# breakout_v3.net
KiCad netlist of a schematic drawn in EAGLE
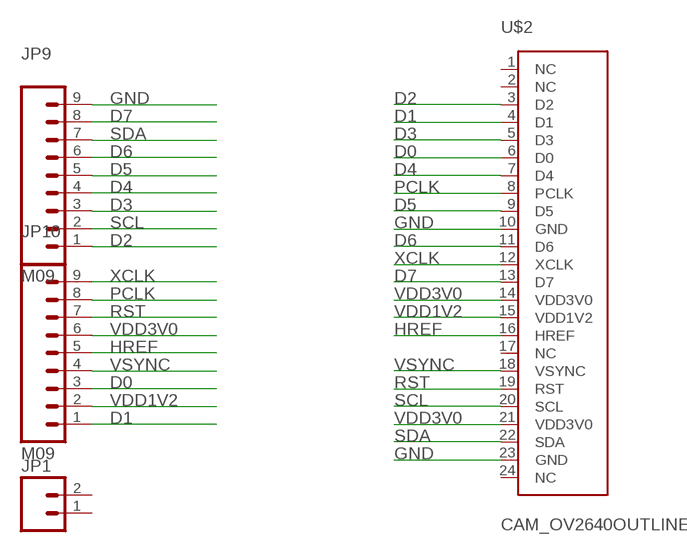
[diagram p0: schematic, sheet 1]

(export (version "E")
  (design (tool "Eeschema 10.0.6"))
  (components
    (comp (ref "JP1")
      (value "M02PTH")
      (footprint "eagle-import:1X02")
      (libsource (lib "eagle-import") (part "M02PTH"))
    )
    (comp (ref "JP9")
      (value "M09")
      (footprint "eagle-import:1X09")
      (libsource (lib "eagle-import") (part "M09"))
    )
    (comp (ref "JP10")
      (value "M09")
      (footprint "eagle-import:1X09")
      (libsource (lib "eagle-import") (part "M09"))
    )
    (comp (ref "U$2")
      (value "CAM_OV2640OUTLINE")
      (footprint "eagle-import:CAM_CONN")
      (libsource (lib "eagle-import") (part "CAM_OV2640OUTLINE"))
    )
  )
  (nets
    (net (code "1") (name "/D0") (class "Default")
      (node (ref "JP10") (pin "3") (pinfunction "3_3") (pintype "passive"))
      (node (ref "U$2") (pin "6") (pinfunction "D0_6") (pintype "bidirectional"))
    )
    (net (code "2") (name "/D1") (class "Default")
      (node (ref "JP10") (pin "1") (pinfunction "1_1") (pintype "passive"))
      (node (ref "U$2") (pin "4") (pinfunction "D1_4") (pintype "bidirectional"))
    )
    (net (code "3") (name "/D2") (class "Default")
      (node (ref "JP9") (pin "1") (pinfunction "1_1") (pintype "passive"))
      (node (ref "U$2") (pin "3") (pinfunction "D2_3") (pintype "bidirectional"))
    )
    (net (code "4") (name "/D3") (class "Default")
      (node (ref "JP9") (pin "3") (pinfunction "3_3") (pintype "passive"))
      (node (ref "U$2") (pin "5") (pinfunction "D3_5") (pintype "bidirectional"))
    )
    (net (code "5") (name "/D4") (class "Default")
      (node (ref "JP9") (pin "4") (pinfunction "4_4") (pintype "passive"))
      (node (ref "U$2") (pin "7") (pinfunction "D4_7") (pintype "bidirectional"))
    )
    (net (code "6") (name "/D5") (class "Default")
      (node (ref "JP9") (pin "5") (pinfunction "5_5") (pintype "passive"))
      (node (ref "U$2") (pin "9") (pinfunction "D5_9") (pintype "bidirectional"))
    )
    (net (code "7") (name "/D6") (class "Default")
      (node (ref "JP9") (pin "6") (pinfunction "6_6") (pintype "passive"))
      (node (ref "U$2") (pin "11") (pinfunction "D6_11") (pintype "bidirectional"))
    )
    (net (code "8") (name "/D7") (class "Default")
      (node (ref "JP9") (pin "8") (pinfunction "8_8") (pintype "passive"))
      (node (ref "U$2") (pin "13") (pinfunction "D7_13") (pintype "bidirectional"))
    )
    (net (code "9") (name "/GND") (class "Default")
      (node (ref "JP9") (pin "9") (pinfunction "9_9") (pintype "passive"))
      (node (ref "U$2") (pin "10") (pinfunction "GND_10") (pintype "bidirectional"))
      (node (ref "U$2") (pin "23") (pinfunction "GND_23") (pintype "bidirectional"))
    )
    (net (code "10") (name "/HREF") (class "Default")
      (node (ref "JP10") (pin "5") (pinfunction "5_5") (pintype "passive"))
      (node (ref "U$2") (pin "16") (pinfunction "HREF_16") (pintype "bidirectional"))
    )
    (net (code "11") (name "/PCLK") (class "Default")
      (node (ref "JP10") (pin "8") (pinfunction "8_8") (pintype "passive"))
      (node (ref "U$2") (pin "8") (pinfunction "PCLK_8") (pintype "bidirectional"))
    )
    (net (code "12") (name "/RST") (class "Default")
      (node (ref "JP10") (pin "7") (pinfunction "7_7") (pintype "passive"))
      (node (ref "U$2") (pin "19") (pinfunction "RST_19") (pintype "bidirectional"))
    )
    (net (code "13") (name "/SCL") (class "Default")
      (node (ref "JP9") (pin "2") (pinfunction "2_2") (pintype "passive"))
      (node (ref "U$2") (pin "20") (pinfunction "SCL_20") (pintype "bidirectional"))
    )
    (net (code "14") (name "/SDA") (class "Default")
      (node (ref "JP9") (pin "7") (pinfunction "7_7") (pintype "passive"))
      (node (ref "U$2") (pin "22") (pinfunction "SDA_22") (pintype "bidirectional"))
    )
    (net (code "15") (name "/VDD1V2") (class "Default")
      (node (ref "JP10") (pin "2") (pinfunction "2_2") (pintype "passive"))
      (node (ref "U$2") (pin "15") (pinfunction "VDD1V2_15") (pintype "bidirectional"))
    )
    (net (code "16") (name "/VDD3V0") (class "Default")
      (node (ref "JP10") (pin "6") (pinfunction "6_6") (pintype "passive"))
      (node (ref "U$2") (pin "14") (pinfunction "VDD3V0_14") (pintype "bidirectional"))
      (node (ref "U$2") (pin "21") (pinfunction "VDD3V0_21") (pintype "bidirectional"))
    )
    (net (code "17") (name "/VSYNC") (class "Default")
      (node (ref "JP10") (pin "4") (pinfunction "4_4") (pintype "passive"))
      (node (ref "U$2") (pin "18") (pinfunction "VSYNC_18") (pintype "bidirectional"))
    )
    (net (code "18") (name "/XCLK") (class "Default")
      (node (ref "JP10") (pin "9") (pinfunction "9_9") (pintype "passive"))
      (node (ref "U$2") (pin "12") (pinfunction "XCLK_12") (pintype "bidirectional"))
    )
    (net (code "19") (name "unconnected-(JP1-Pad1)") (class "Default")
      (node (ref "JP1") (pin "1") (pinfunction "1_1") (pintype "passive"))
    )
    (net (code "20") (name "unconnected-(JP1-Pad2)") (class "Default")
      (node (ref "JP1") (pin "2") (pinfunction "2_2") (pintype "passive"))
    )
    (net (code "21") (name "unconnected-(U$2-NC-Pad1)") (class "Default")
      (node (ref "U$2") (pin "1") (pinfunction "NC_1") (pintype "bidirectional"))
    )
    (net (code "22") (name "unconnected-(U$2-NC-Pad2)") (class "Default")
      (node (ref "U$2") (pin "2") (pinfunction "NC_2") (pintype "bidirectional"))
    )
    (net (code "23") (name "unconnected-(U$2-NC-Pad17)") (class "Default")
      (node (ref "U$2") (pin "17") (pinfunction "NC_17") (pintype "bidirectional"))
    )
    (net (code "24") (name "unconnected-(U$2-NC-Pad24)") (class "Default")
      (node (ref "U$2") (pin "24") (pinfunction "NC_24") (pintype "bidirectional"))
    )
  )
)
